# Noise_Percussion_ctrl.net
KiCad netlist of a schematic drawn in EAGLE
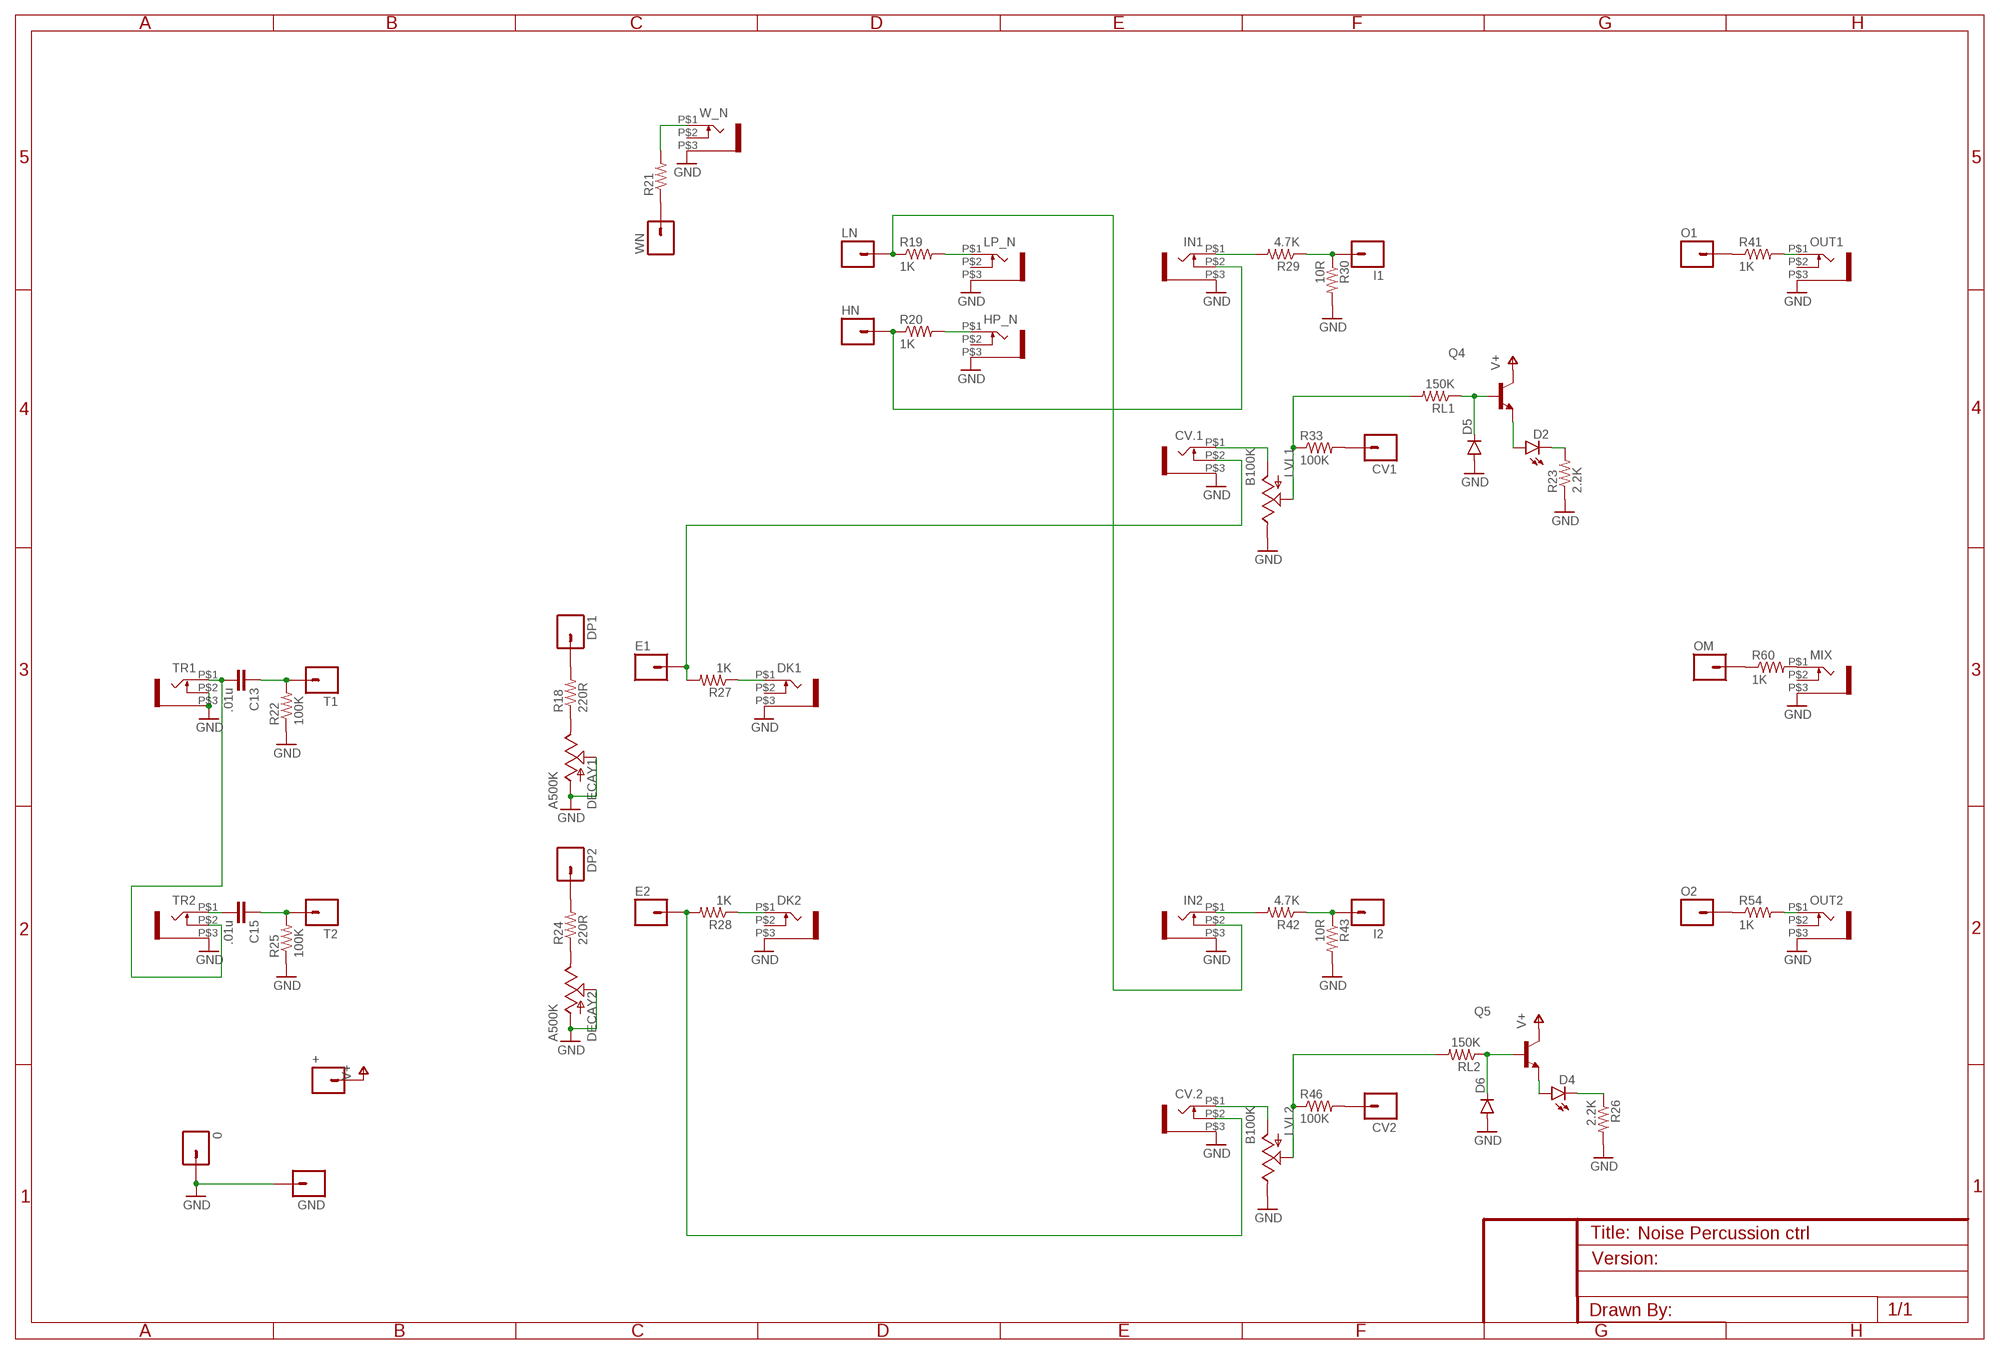
[diagram p0: schematic, sheet 1]

(export (version "E")
  (design (tool "Eeschema 10.0.6"))
  (components
    (comp (ref "+")
      (value "M01PTH")
      (footprint "eagle-import:1X01")
      (libsource (lib "eagle-import") (part "M01PTH"))
    )
    (comp (ref "0")
      (value "M01PTH")
      (footprint "eagle-import:1X01")
      (libsource (lib "eagle-import") (part "M01PTH"))
    )
    (comp (ref "C13")
      (value ".01u")
      (footprint "eagle-import:0805")
      (libsource (lib "eagle-import") (part "CAP0805"))
    )
    (comp (ref "C15")
      (value ".01u")
      (footprint "eagle-import:0805")
      (libsource (lib "eagle-import") (part "CAP0805"))
    )
    (comp (ref "CV.1")
      (value "WQP-PJ301M-12_JACK")
      (footprint "eagle-import:WQP-PJ301M-12_JACK")
      (libsource (lib "eagle-import") (part "WQP-PJ301M-12_JACK"))
    )
    (comp (ref "CV.2")
      (value "WQP-PJ301M-12_JACK")
      (footprint "eagle-import:WQP-PJ301M-12_JACK")
      (libsource (lib "eagle-import") (part "WQP-PJ301M-12_JACK"))
    )
    (comp (ref "CV1")
      (value "M01PTH")
      (footprint "eagle-import:1X01")
      (libsource (lib "eagle-import") (part "M01PTH"))
    )
    (comp (ref "CV2")
      (value "M01PTH")
      (footprint "eagle-import:1X01")
      (libsource (lib "eagle-import") (part "M01PTH"))
    )
    (comp (ref "D2")
      (value "LED3MM")
      (footprint "eagle-import:LED3MM")
      (libsource (lib "eagle-import") (part "LED3MM"))
    )
    (comp (ref "D4")
      (value "LED3MM")
      (footprint "eagle-import:LED3MM")
      (libsource (lib "eagle-import") (part "LED3MM"))
    )
    (comp (ref "D5")
      (value "DIODESOD123")
      (footprint "eagle-import:SOD-123")
      (libsource (lib "eagle-import") (part "DIODESOD123"))
    )
    (comp (ref "D6")
      (value "DIODESOD123")
      (footprint "eagle-import:SOD-123")
      (libsource (lib "eagle-import") (part "DIODESOD123"))
    )
    (comp (ref "DECAY1")
      (value "A500K")
      (footprint "eagle-import:ALPS_POT")
      (libsource (lib "eagle-import") (part "POT"))
    )
    (comp (ref "DECAY2")
      (value "A500K")
      (footprint "eagle-import:ALPS_POT")
      (libsource (lib "eagle-import") (part "POT"))
    )
    (comp (ref "DK1")
      (value "WQP-PJ301M-12_JACK")
      (footprint "eagle-import:WQP-PJ301M-12_JACK")
      (libsource (lib "eagle-import") (part "WQP-PJ301M-12_JACK"))
    )
    (comp (ref "DK2")
      (value "WQP-PJ301M-12_JACK")
      (footprint "eagle-import:WQP-PJ301M-12_JACK")
      (libsource (lib "eagle-import") (part "WQP-PJ301M-12_JACK"))
    )
    (comp (ref "DP1")
      (value "M01PTH")
      (footprint "eagle-import:1X01")
      (libsource (lib "eagle-import") (part "M01PTH"))
    )
    (comp (ref "DP2")
      (value "M01PTH")
      (footprint "eagle-import:1X01")
      (libsource (lib "eagle-import") (part "M01PTH"))
    )
    (comp (ref "E1")
      (value "M01PTH")
      (footprint "eagle-import:1X01")
      (libsource (lib "eagle-import") (part "M01PTH"))
    )
    (comp (ref "E2")
      (value "M01PTH")
      (footprint "eagle-import:1X01")
      (libsource (lib "eagle-import") (part "M01PTH"))
    )
    (comp (ref "GND")
      (value "M01PTH")
      (footprint "eagle-import:1X01")
      (libsource (lib "eagle-import") (part "M01PTH"))
    )
    (comp (ref "HN")
      (value "M01PTH")
      (footprint "eagle-import:1X01")
      (libsource (lib "eagle-import") (part "M01PTH"))
    )
    (comp (ref "HP_N")
      (value "WQP-PJ301M-12_JACK")
      (footprint "eagle-import:WQP-PJ301M-12_JACK")
      (libsource (lib "eagle-import") (part "WQP-PJ301M-12_JACK"))
    )
    (comp (ref "I1")
      (value "M01PTH")
      (footprint "eagle-import:1X01")
      (libsource (lib "eagle-import") (part "M01PTH"))
    )
    (comp (ref "I2")
      (value "M01PTH")
      (footprint "eagle-import:1X01")
      (libsource (lib "eagle-import") (part "M01PTH"))
    )
    (comp (ref "IN1")
      (value "WQP-PJ301M-12_JACK")
      (footprint "eagle-import:WQP-PJ301M-12_JACK")
      (libsource (lib "eagle-import") (part "WQP-PJ301M-12_JACK"))
    )
    (comp (ref "IN2")
      (value "WQP-PJ301M-12_JACK")
      (footprint "eagle-import:WQP-PJ301M-12_JACK")
      (libsource (lib "eagle-import") (part "WQP-PJ301M-12_JACK"))
    )
    (comp (ref "LN")
      (value "M01PTH")
      (footprint "eagle-import:1X01")
      (libsource (lib "eagle-import") (part "M01PTH"))
    )
    (comp (ref "LP_N")
      (value "WQP-PJ301M-12_JACK")
      (footprint "eagle-import:WQP-PJ301M-12_JACK")
      (libsource (lib "eagle-import") (part "WQP-PJ301M-12_JACK"))
    )
    (comp (ref "LVL1")
      (value "B100K")
      (footprint "eagle-import:ALPS_POT")
      (libsource (lib "eagle-import") (part "POT"))
    )
    (comp (ref "LVL2")
      (value "B100K")
      (footprint "eagle-import:ALPS_POT")
      (libsource (lib "eagle-import") (part "POT"))
    )
    (comp (ref "MIX")
      (value "WQP-PJ301M-12_JACK")
      (footprint "eagle-import:WQP-PJ301M-12_JACK")
      (libsource (lib "eagle-import") (part "WQP-PJ301M-12_JACK"))
    )
    (comp (ref "O1")
      (value "M01PTH")
      (footprint "eagle-import:1X01")
      (libsource (lib "eagle-import") (part "M01PTH"))
    )
    (comp (ref "O2")
      (value "M01PTH")
      (footprint "eagle-import:1X01")
      (libsource (lib "eagle-import") (part "M01PTH"))
    )
    (comp (ref "OM")
      (value "M01PTH")
      (footprint "eagle-import:1X01")
      (libsource (lib "eagle-import") (part "M01PTH"))
    )
    (comp (ref "OUT1")
      (value "WQP-PJ301M-12_JACK")
      (footprint "eagle-import:WQP-PJ301M-12_JACK")
      (libsource (lib "eagle-import") (part "WQP-PJ301M-12_JACK"))
    )
    (comp (ref "OUT2")
      (value "WQP-PJ301M-12_JACK")
      (footprint "eagle-import:WQP-PJ301M-12_JACK")
      (libsource (lib "eagle-import") (part "WQP-PJ301M-12_JACK"))
    )
    (comp (ref "Q4")
      (value "MMBT3904LT1-NPN-SOT23-BEC")
      (footprint "eagle-import:SOT23-BEC")
      (libsource (lib "eagle-import") (part "-NPN-SOT23-BECMMBT3904LT1"))
    )
    (comp (ref "Q5")
      (value "MMBT3904LT1-NPN-SOT23-BEC")
      (footprint "eagle-import:SOT23-BEC")
      (libsource (lib "eagle-import") (part "-NPN-SOT23-BECMMBT3904LT1"))
    )
    (comp (ref "R18")
      (value "220R")
      (footprint "eagle-import:0805")
      (libsource (lib "eagle-import") (part "RESISTOR0805-RES"))
    )
    (comp (ref "R19")
      (value "1K")
      (footprint "eagle-import:0805")
      (libsource (lib "eagle-import") (part "RESISTOR0805-RES"))
    )
    (comp (ref "R20")
      (value "1K")
      (footprint "eagle-import:0805")
      (libsource (lib "eagle-import") (part "RESISTOR0805-RES"))
    )
    (comp (ref "R21")
      (value "RESISTOR0805-RES")
      (footprint "eagle-import:0805")
      (libsource (lib "eagle-import") (part "RESISTOR0805-RES"))
    )
    (comp (ref "R22")
      (value "100K")
      (footprint "eagle-import:0805")
      (libsource (lib "eagle-import") (part "RESISTOR0805-RES"))
    )
    (comp (ref "R23")
      (value "2.2K")
      (footprint "eagle-import:0805")
      (libsource (lib "eagle-import") (part "RESISTOR0805-RES"))
    )
    (comp (ref "R24")
      (value "220R")
      (footprint "eagle-import:0805")
      (libsource (lib "eagle-import") (part "RESISTOR0805-RES"))
    )
    (comp (ref "R25")
      (value "100K")
      (footprint "eagle-import:0805")
      (libsource (lib "eagle-import") (part "RESISTOR0805-RES"))
    )
    (comp (ref "R26")
      (value "2.2K")
      (footprint "eagle-import:0805")
      (libsource (lib "eagle-import") (part "RESISTOR0805-RES"))
    )
    (comp (ref "R27")
      (value "1K")
      (footprint "eagle-import:0805")
      (libsource (lib "eagle-import") (part "RESISTOR0805-RES"))
    )
    (comp (ref "R28")
      (value "1K")
      (footprint "eagle-import:0805")
      (libsource (lib "eagle-import") (part "RESISTOR0805-RES"))
    )
    (comp (ref "R29")
      (value "4.7K")
      (footprint "eagle-import:0805")
      (libsource (lib "eagle-import") (part "RESISTOR0805-RES"))
    )
    (comp (ref "R30")
      (value "10R")
      (footprint "eagle-import:0805")
      (libsource (lib "eagle-import") (part "RESISTOR0805-RES"))
    )
    (comp (ref "R33")
      (value "100K")
      (footprint "eagle-import:0805")
      (libsource (lib "eagle-import") (part "RESISTOR0805-RES"))
    )
    (comp (ref "R41")
      (value "1K")
      (footprint "eagle-import:0805")
      (libsource (lib "eagle-import") (part "RESISTOR0805-RES"))
    )
    (comp (ref "R42")
      (value "4.7K")
      (footprint "eagle-import:0805")
      (libsource (lib "eagle-import") (part "RESISTOR0805-RES"))
    )
    (comp (ref "R43")
      (value "10R")
      (footprint "eagle-import:0805")
      (libsource (lib "eagle-import") (part "RESISTOR0805-RES"))
    )
    (comp (ref "R46")
      (value "100K")
      (footprint "eagle-import:0805")
      (libsource (lib "eagle-import") (part "RESISTOR0805-RES"))
    )
    (comp (ref "R54")
      (value "1K")
      (footprint "eagle-import:0805")
      (libsource (lib "eagle-import") (part "RESISTOR0805-RES"))
    )
    (comp (ref "R60")
      (value "1K")
      (footprint "eagle-import:0805")
      (libsource (lib "eagle-import") (part "RESISTOR0805-RES"))
    )
    (comp (ref "RL1")
      (value "150K")
      (footprint "eagle-import:0805")
      (libsource (lib "eagle-import") (part "RESISTOR0805-RES"))
    )
    (comp (ref "RL2")
      (value "150K")
      (footprint "eagle-import:0805")
      (libsource (lib "eagle-import") (part "RESISTOR0805-RES"))
    )
    (comp (ref "T1")
      (value "M01PTH")
      (footprint "eagle-import:1X01")
      (libsource (lib "eagle-import") (part "M01PTH"))
    )
    (comp (ref "T2")
      (value "M01PTH")
      (footprint "eagle-import:1X01")
      (libsource (lib "eagle-import") (part "M01PTH"))
    )
    (comp (ref "TR1")
      (value "WQP-PJ301M-12_JACK")
      (footprint "eagle-import:WQP-PJ301M-12_JACK")
      (libsource (lib "eagle-import") (part "WQP-PJ301M-12_JACK"))
    )
    (comp (ref "TR2")
      (value "WQP-PJ301M-12_JACK")
      (footprint "eagle-import:WQP-PJ301M-12_JACK")
      (libsource (lib "eagle-import") (part "WQP-PJ301M-12_JACK"))
    )
    (comp (ref "WN")
      (value "M01PTH")
      (footprint "eagle-import:1X01")
      (libsource (lib "eagle-import") (part "M01PTH"))
    )
    (comp (ref "W_N")
      (value "WQP-PJ301M-12_JACK")
      (footprint "eagle-import:WQP-PJ301M-12_JACK")
      (libsource (lib "eagle-import") (part "WQP-PJ301M-12_JACK"))
    )
  )
  (nets
    (net (code "1") (name "GND") (class "Default")
      (node (ref "0") (pin "1") (pinfunction "1_1") (pintype "passive"))
      (node (ref "CV.1") (pin "P$3") (pinfunction "1_P$3") (pintype "passive"))
      (node (ref "CV.2") (pin "P$3") (pinfunction "1_P$3") (pintype "passive"))
      (node (ref "D5") (pin "A") (pinfunction "A_A") (pintype "passive"))
      (node (ref "D6") (pin "A") (pinfunction "A_A") (pintype "passive"))
      (node (ref "DECAY1") (pin "P$2") (pinfunction "S_P$2") (pintype "passive"))
      (node (ref "DECAY1") (pin "P$3") (pinfunction "A_P$3") (pintype "passive"))
      (node (ref "DECAY2") (pin "P$2") (pinfunction "S_P$2") (pintype "passive"))
      (node (ref "DECAY2") (pin "P$3") (pinfunction "A_P$3") (pintype "passive"))
      (node (ref "DK1") (pin "P$3") (pinfunction "1_P$3") (pintype "passive"))
      (node (ref "DK2") (pin "P$3") (pinfunction "1_P$3") (pintype "passive"))
      (node (ref "GND") (pin "1") (pinfunction "1_1") (pintype "passive"))
      (node (ref "HP_N") (pin "P$3") (pinfunction "1_P$3") (pintype "passive"))
      (node (ref "IN1") (pin "P$3") (pinfunction "1_P$3") (pintype "passive"))
      (node (ref "IN2") (pin "P$3") (pinfunction "1_P$3") (pintype "passive"))
      (node (ref "LP_N") (pin "P$3") (pinfunction "1_P$3") (pintype "passive"))
      (node (ref "LVL1") (pin "P$1") (pinfunction "E_P$1") (pintype "passive"))
      (node (ref "LVL2") (pin "P$1") (pinfunction "E_P$1") (pintype "passive"))
      (node (ref "MIX") (pin "P$3") (pinfunction "1_P$3") (pintype "passive"))
      (node (ref "OUT1") (pin "P$3") (pinfunction "1_P$3") (pintype "passive"))
      (node (ref "OUT2") (pin "P$3") (pinfunction "1_P$3") (pintype "passive"))
      (node (ref "R22") (pin "1") (pinfunction "1_1") (pintype "passive"))
      (node (ref "R23") (pin "1") (pinfunction "1_1") (pintype "passive"))
      (node (ref "R25") (pin "1") (pinfunction "1_1") (pintype "passive"))
      (node (ref "R26") (pin "2") (pinfunction "2_2") (pintype "passive"))
      (node (ref "R30") (pin "2") (pinfunction "2_2") (pintype "passive"))
      (node (ref "R43") (pin "2") (pinfunction "2_2") (pintype "passive"))
      (node (ref "TR1") (pin "P$2") (pinfunction "3_P$2") (pintype "passive"))
      (node (ref "TR1") (pin "P$3") (pinfunction "1_P$3") (pintype "passive"))
      (node (ref "TR2") (pin "P$3") (pinfunction "1_P$3") (pintype "passive"))
      (node (ref "W_N") (pin "P$3") (pinfunction "1_P$3") (pintype "passive"))
    )
    (net (code "2") (name "Net-(C13-Pad1)") (class "Default")
      (node (ref "C13") (pin "1") (pinfunction "1_1") (pintype "passive"))
      (node (ref "R22") (pin "2") (pinfunction "2_2") (pintype "passive"))
      (node (ref "T1") (pin "1") (pinfunction "1_1") (pintype "passive"))
    )
    (net (code "3") (name "Net-(C15-Pad1)") (class "Default")
      (node (ref "C15") (pin "1") (pinfunction "1_1") (pintype "passive"))
      (node (ref "R25") (pin "2") (pinfunction "2_2") (pintype "passive"))
      (node (ref "T2") (pin "1") (pinfunction "1_1") (pintype "passive"))
    )
    (net (code "4") (name "Net-(CV.1-2)") (class "Default")
      (node (ref "CV.1") (pin "P$1") (pinfunction "2_P$1") (pintype "passive"))
      (node (ref "LVL1") (pin "P$3") (pinfunction "A_P$3") (pintype "passive"))
    )
    (net (code "5") (name "Net-(CV.1-3)") (class "Default")
      (node (ref "CV.1") (pin "P$2") (pinfunction "3_P$2") (pintype "passive"))
      (node (ref "E1") (pin "1") (pinfunction "1_1") (pintype "passive"))
      (node (ref "R27") (pin "2") (pinfunction "2_2") (pintype "passive"))
    )
    (net (code "6") (name "Net-(CV.2-2)") (class "Default")
      (node (ref "CV.2") (pin "P$1") (pinfunction "2_P$1") (pintype "passive"))
      (node (ref "LVL2") (pin "P$3") (pinfunction "A_P$3") (pintype "passive"))
    )
    (net (code "7") (name "Net-(CV.2-3)") (class "Default")
      (node (ref "CV.2") (pin "P$2") (pinfunction "3_P$2") (pintype "passive"))
      (node (ref "E2") (pin "1") (pinfunction "1_1") (pintype "passive"))
      (node (ref "R28") (pin "2") (pinfunction "2_2") (pintype "passive"))
    )
    (net (code "8") (name "Net-(CV1-Pad1)") (class "Default")
      (node (ref "CV1") (pin "1") (pinfunction "1_1") (pintype "passive"))
      (node (ref "R33") (pin "2") (pinfunction "2_2") (pintype "passive"))
    )
    (net (code "9") (name "Net-(CV2-Pad1)") (class "Default")
      (node (ref "CV2") (pin "1") (pinfunction "1_1") (pintype "passive"))
      (node (ref "R46") (pin "2") (pinfunction "2_2") (pintype "passive"))
    )
    (net (code "10") (name "Net-(D2-C)") (class "Default")
      (node (ref "D2") (pin "K") (pinfunction "C_K") (pintype "passive"))
      (node (ref "R23") (pin "2") (pinfunction "2_2") (pintype "passive"))
    )
    (net (code "11") (name "Net-(D2-PadA)") (class "Default")
      (node (ref "D2") (pin "A") (pinfunction "A_A") (pintype "passive"))
      (node (ref "Q4") (pin "E") (pinfunction "E_E") (pintype "passive"))
    )
    (net (code "12") (name "Net-(D4-C)") (class "Default")
      (node (ref "D4") (pin "K") (pinfunction "C_K") (pintype "passive"))
      (node (ref "R26") (pin "1") (pinfunction "1_1") (pintype "passive"))
    )
    (net (code "13") (name "Net-(D4-PadA)") (class "Default")
      (node (ref "D4") (pin "A") (pinfunction "A_A") (pintype "passive"))
      (node (ref "Q5") (pin "E") (pinfunction "E_E") (pintype "passive"))
    )
    (net (code "14") (name "Net-(D5-PadC)") (class "Default")
      (node (ref "D5") (pin "C") (pinfunction "C_C") (pintype "passive"))
      (node (ref "Q4") (pin "B") (pinfunction "B_B") (pintype "passive"))
      (node (ref "RL1") (pin "1") (pinfunction "1_1") (pintype "passive"))
    )
    (net (code "15") (name "Net-(D6-PadC)") (class "Default")
      (node (ref "D6") (pin "C") (pinfunction "C_C") (pintype "passive"))
      (node (ref "Q5") (pin "B") (pinfunction "B_B") (pintype "passive"))
      (node (ref "RL2") (pin "1") (pinfunction "1_1") (pintype "passive"))
    )
    (net (code "16") (name "Net-(DECAY1-E)") (class "Default")
      (node (ref "DECAY1") (pin "P$1") (pinfunction "E_P$1") (pintype "passive"))
      (node (ref "R18") (pin "1") (pinfunction "1_1") (pintype "passive"))
    )
    (net (code "17") (name "Net-(DECAY2-E)") (class "Default")
      (node (ref "DECAY2") (pin "P$1") (pinfunction "E_P$1") (pintype "passive"))
      (node (ref "R24") (pin "1") (pinfunction "1_1") (pintype "passive"))
    )
    (net (code "18") (name "Net-(DK1-2)") (class "Default")
      (node (ref "DK1") (pin "P$1") (pinfunction "2_P$1") (pintype "passive"))
      (node (ref "R27") (pin "1") (pinfunction "1_1") (pintype "passive"))
    )
    (net (code "19") (name "Net-(DK2-2)") (class "Default")
      (node (ref "DK2") (pin "P$1") (pinfunction "2_P$1") (pintype "passive"))
      (node (ref "R28") (pin "1") (pinfunction "1_1") (pintype "passive"))
    )
    (net (code "20") (name "Net-(DP1-Pad1)") (class "Default")
      (node (ref "DP1") (pin "1") (pinfunction "1_1") (pintype "passive"))
      (node (ref "R18") (pin "2") (pinfunction "2_2") (pintype "passive"))
    )
    (net (code "21") (name "Net-(DP2-Pad1)") (class "Default")
      (node (ref "DP2") (pin "1") (pinfunction "1_1") (pintype "passive"))
      (node (ref "R24") (pin "2") (pinfunction "2_2") (pintype "passive"))
    )
    (net (code "22") (name "Net-(HP_N-2)") (class "Default")
      (node (ref "HP_N") (pin "P$1") (pinfunction "2_P$1") (pintype "passive"))
      (node (ref "R20") (pin "2") (pinfunction "2_2") (pintype "passive"))
    )
    (net (code "23") (name "Net-(I1-Pad1)") (class "Default")
      (node (ref "I1") (pin "1") (pinfunction "1_1") (pintype "passive"))
      (node (ref "R29") (pin "1") (pinfunction "1_1") (pintype "passive"))
      (node (ref "R30") (pin "1") (pinfunction "1_1") (pintype "passive"))
    )
    (net (code "24") (name "Net-(I2-Pad1)") (class "Default")
      (node (ref "I2") (pin "1") (pinfunction "1_1") (pintype "passive"))
      (node (ref "R42") (pin "1") (pinfunction "1_1") (pintype "passive"))
      (node (ref "R43") (pin "1") (pinfunction "1_1") (pintype "passive"))
    )
    (net (code "25") (name "Net-(IN1-2)") (class "Default")
      (node (ref "IN1") (pin "P$1") (pinfunction "2_P$1") (pintype "passive"))
      (node (ref "R29") (pin "2") (pinfunction "2_2") (pintype "passive"))
    )
    (net (code "26") (name "Net-(IN1-3)") (class "Default")
      (node (ref "HN") (pin "1") (pinfunction "1_1") (pintype "passive"))
      (node (ref "IN1") (pin "P$2") (pinfunction "3_P$2") (pintype "passive"))
      (node (ref "R20") (pin "1") (pinfunction "1_1") (pintype "passive"))
    )
    (net (code "27") (name "Net-(IN2-2)") (class "Default")
      (node (ref "IN2") (pin "P$1") (pinfunction "2_P$1") (pintype "passive"))
      (node (ref "R42") (pin "2") (pinfunction "2_2") (pintype "passive"))
    )
    (net (code "28") (name "Net-(IN2-3)") (class "Default")
      (node (ref "IN2") (pin "P$2") (pinfunction "3_P$2") (pintype "passive"))
      (node (ref "LN") (pin "1") (pinfunction "1_1") (pintype "passive"))
      (node (ref "R19") (pin "1") (pinfunction "1_1") (pintype "passive"))
    )
    (net (code "29") (name "Net-(LP_N-2)") (class "Default")
      (node (ref "LP_N") (pin "P$1") (pinfunction "2_P$1") (pintype "passive"))
      (node (ref "R19") (pin "2") (pinfunction "2_2") (pintype "passive"))
    )
    (net (code "30") (name "Net-(LVL1-S)") (class "Default")
      (node (ref "LVL1") (pin "P$2") (pinfunction "S_P$2") (pintype "passive"))
      (node (ref "R33") (pin "1") (pinfunction "1_1") (pintype "passive"))
      (node (ref "RL1") (pin "2") (pinfunction "2_2") (pintype "passive"))
    )
    (net (code "31") (name "Net-(LVL2-S)") (class "Default")
      (node (ref "LVL2") (pin "P$2") (pinfunction "S_P$2") (pintype "passive"))
      (node (ref "R46") (pin "1") (pinfunction "1_1") (pintype "passive"))
      (node (ref "RL2") (pin "2") (pinfunction "2_2") (pintype "passive"))
    )
    (net (code "32") (name "Net-(MIX-2)") (class "Default")
      (node (ref "MIX") (pin "P$1") (pinfunction "2_P$1") (pintype "passive"))
      (node (ref "R60") (pin "2") (pinfunction "2_2") (pintype "passive"))
    )
    (net (code "33") (name "Net-(O1-Pad1)") (class "Default")
      (node (ref "O1") (pin "1") (pinfunction "1_1") (pintype "passive"))
      (node (ref "R41") (pin "1") (pinfunction "1_1") (pintype "passive"))
    )
    (net (code "34") (name "Net-(O2-Pad1)") (class "Default")
      (node (ref "O2") (pin "1") (pinfunction "1_1") (pintype "passive"))
      (node (ref "R54") (pin "1") (pinfunction "1_1") (pintype "passive"))
    )
    (net (code "35") (name "Net-(OM-Pad1)") (class "Default")
      (node (ref "OM") (pin "1") (pinfunction "1_1") (pintype "passive"))
      (node (ref "R60") (pin "1") (pinfunction "1_1") (pintype "passive"))
    )
    (net (code "36") (name "Net-(OUT1-2)") (class "Default")
      (node (ref "OUT1") (pin "P$1") (pinfunction "2_P$1") (pintype "passive"))
      (node (ref "R41") (pin "2") (pinfunction "2_2") (pintype "passive"))
    )
    (net (code "37") (name "Net-(OUT2-2)") (class "Default")
      (node (ref "OUT2") (pin "P$1") (pinfunction "2_P$1") (pintype "passive"))
      (node (ref "R54") (pin "2") (pinfunction "2_2") (pintype "passive"))
    )
    (net (code "38") (name "Net-(R21-Pad1)") (class "Default")
      (node (ref "R21") (pin "1") (pinfunction "1_1") (pintype "passive"))
      (node (ref "WN") (pin "1") (pinfunction "1_1") (pintype "passive"))
    )
    (net (code "39") (name "Net-(TR1-2)") (class "Default")
      (node (ref "C13") (pin "2") (pinfunction "2_2") (pintype "passive"))
      (node (ref "TR1") (pin "P$1") (pinfunction "2_P$1") (pintype "passive"))
      (node (ref "TR2") (pin "P$2") (pinfunction "3_P$2") (pintype "passive"))
    )
    (net (code "40") (name "Net-(TR2-2)") (class "Default")
      (node (ref "C15") (pin "2") (pinfunction "2_2") (pintype "passive"))
      (node (ref "TR2") (pin "P$1") (pinfunction "2_P$1") (pintype "passive"))
    )
    (net (code "41") (name "Net-(W_N-2)") (class "Default")
      (node (ref "R21") (pin "2") (pinfunction "2_2") (pintype "passive"))
      (node (ref "W_N") (pin "P$1") (pinfunction "2_P$1") (pintype "passive"))
    )
    (net (code "42") (name "V+") (class "Default")
      (node (ref "+") (pin "1") (pinfunction "1_1") (pintype "passive"))
      (node (ref "Q4") (pin "C") (pinfunction "C_C") (pintype "passive"))
      (node (ref "Q5") (pin "C") (pinfunction "C_C") (pintype "passive"))
    )
    (net (code "43") (name "unconnected-(DK1-3-PadP$2)") (class "Default")
      (node (ref "DK1") (pin "P$2") (pinfunction "3_P$2") (pintype "passive"))
    )
    (net (code "44") (name "unconnected-(DK2-3-PadP$2)") (class "Default")
      (node (ref "DK2") (pin "P$2") (pinfunction "3_P$2") (pintype "passive"))
    )
    (net (code "45") (name "unconnected-(HP_N-3-PadP$2)") (class "Default")
      (node (ref "HP_N") (pin "P$2") (pinfunction "3_P$2") (pintype "passive"))
    )
    (net (code "46") (name "unconnected-(LP_N-3-PadP$2)") (class "Default")
      (node (ref "LP_N") (pin "P$2") (pinfunction "3_P$2") (pintype "passive"))
    )
    (net (code "47") (name "unconnected-(MIX-3-PadP$2)") (class "Default")
      (node (ref "MIX") (pin "P$2") (pinfunction "3_P$2") (pintype "passive"))
    )
    (net (code "48") (name "unconnected-(OUT1-3-PadP$2)") (class "Default")
      (node (ref "OUT1") (pin "P$2") (pinfunction "3_P$2") (pintype "passive"))
    )
    (net (code "49") (name "unconnected-(OUT2-3-PadP$2)") (class "Default")
      (node (ref "OUT2") (pin "P$2") (pinfunction "3_P$2") (pintype "passive"))
    )
    (net (code "50") (name "unconnected-(W_N-3-PadP$2)") (class "Default")
      (node (ref "W_N") (pin "P$2") (pinfunction "3_P$2") (pintype "passive"))
    )
  )
)
